# External_MIDI_Interface.net
KiCad netlist of a schematic drawn in EasyEDA
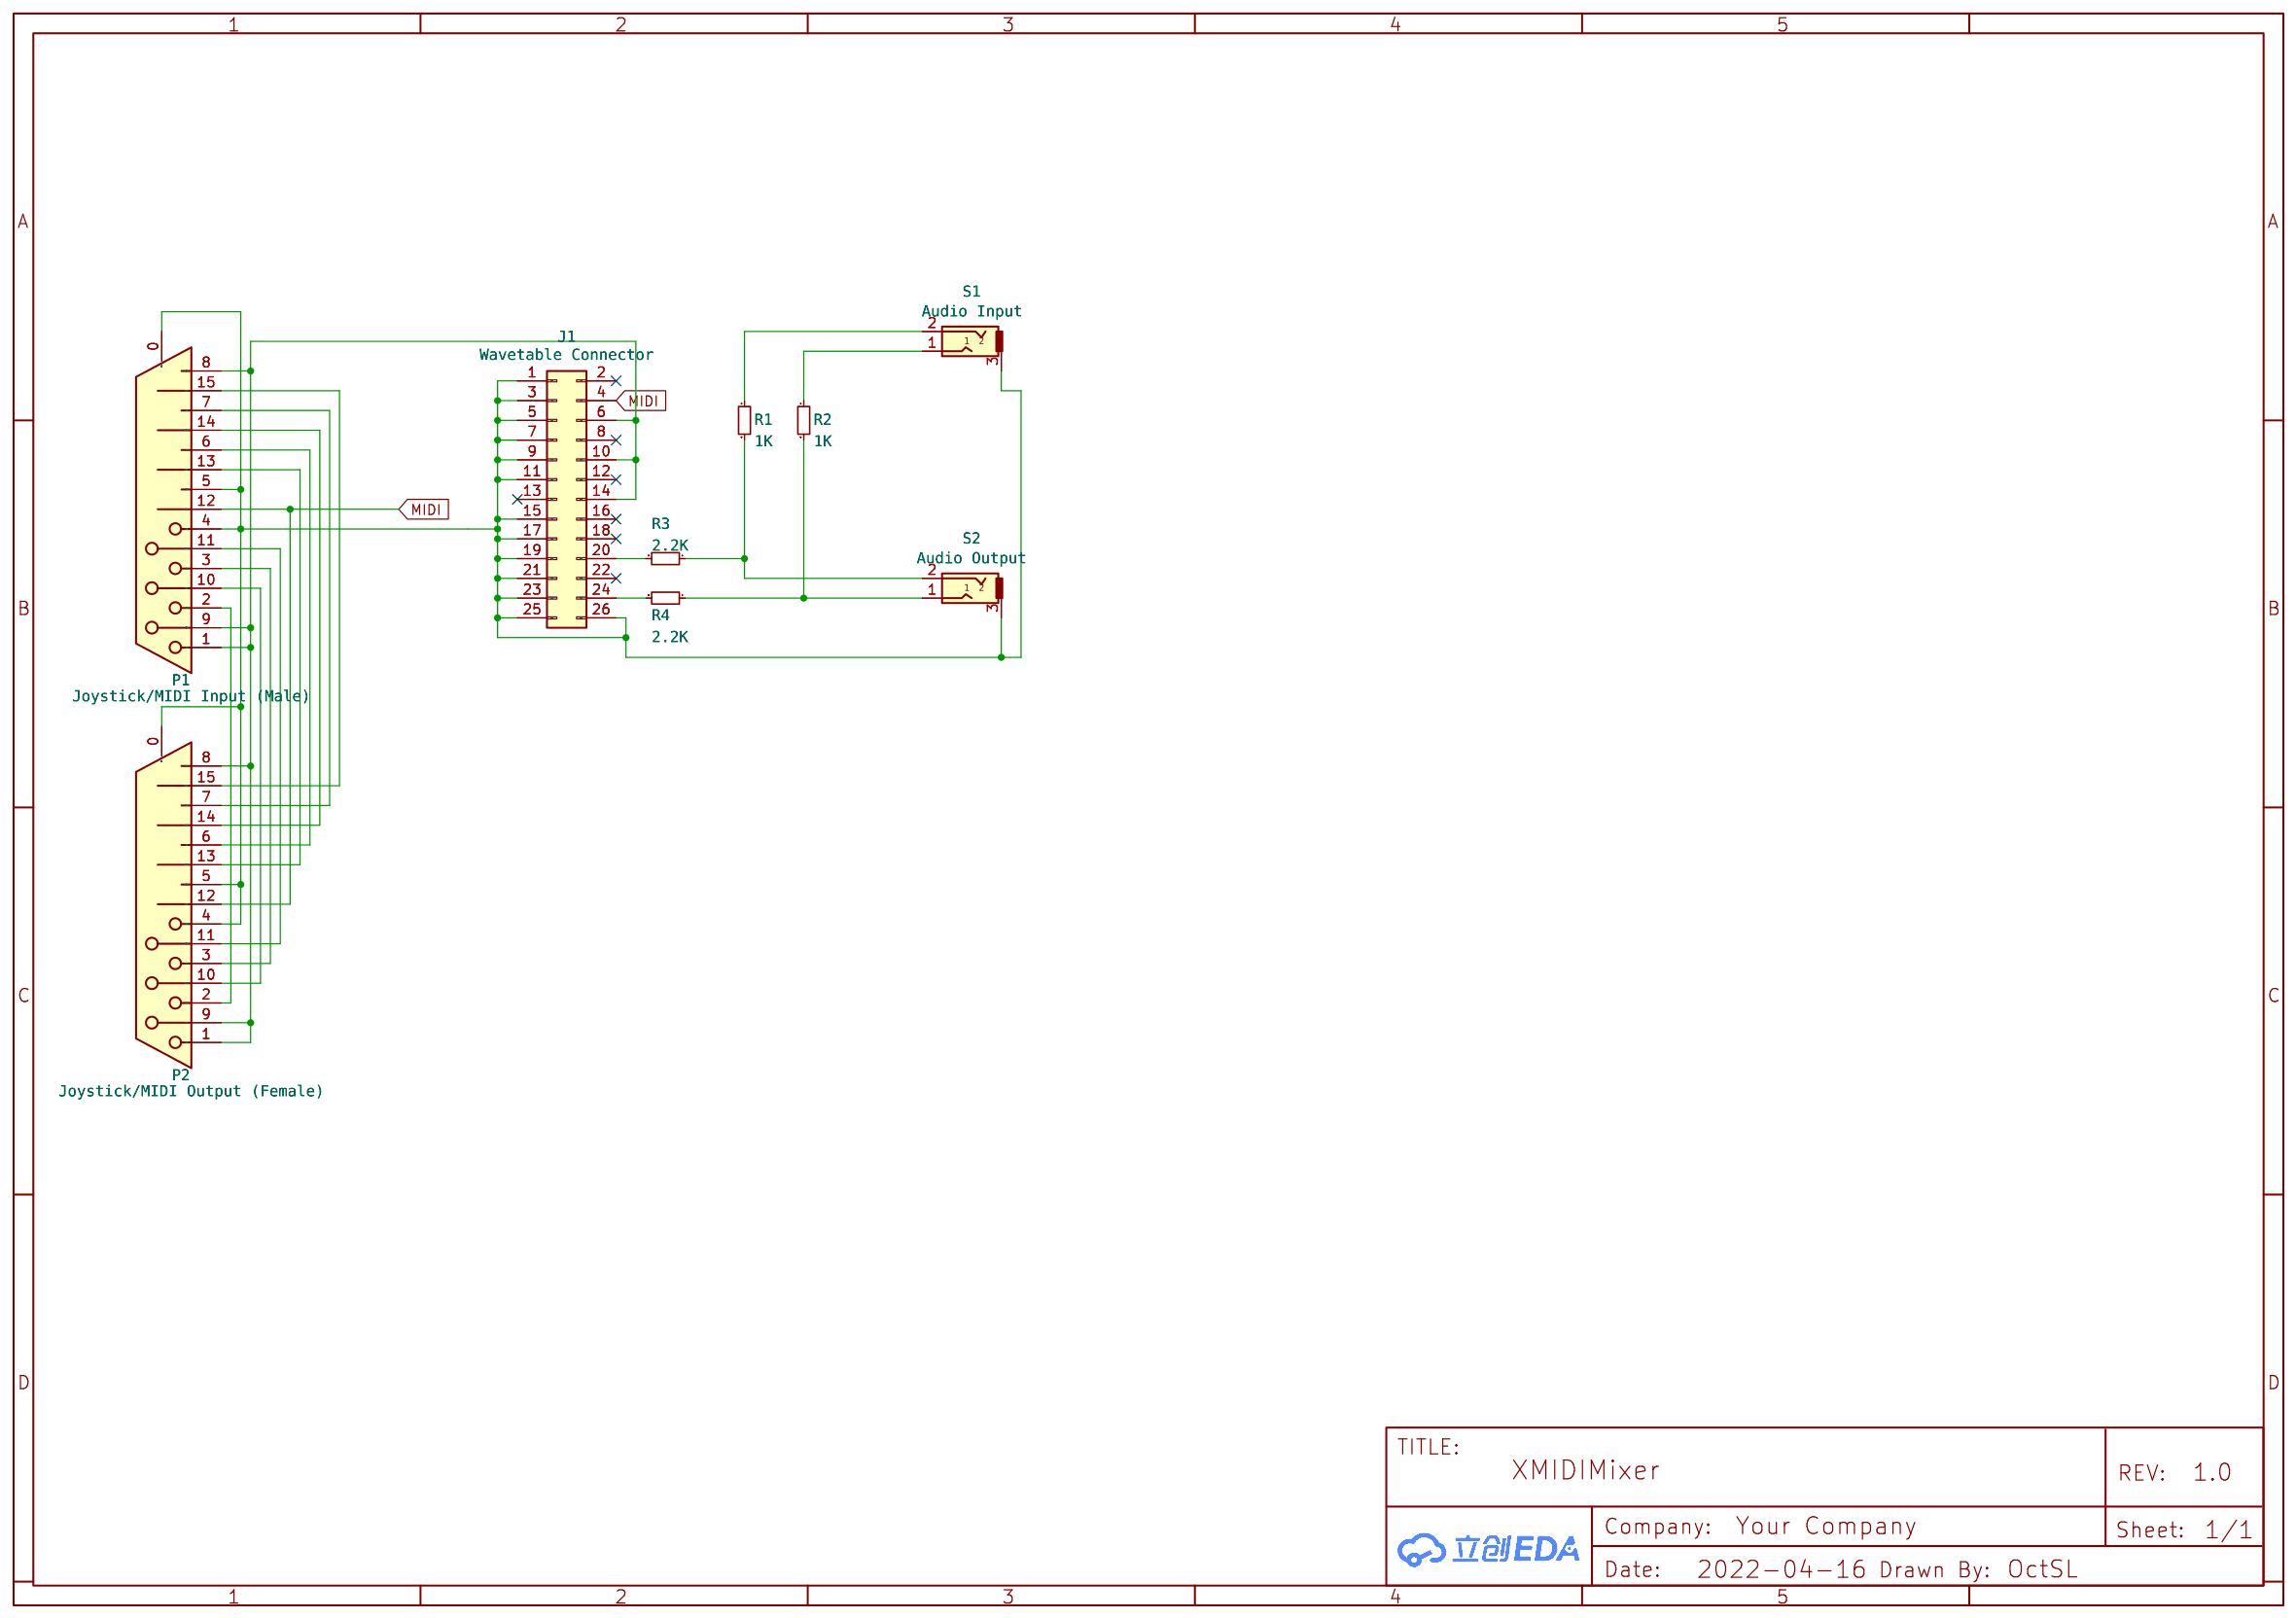
[diagram p0: schematic sheet]

(export (version "E")
  (design (tool "Eeschema 10.0.6"))
  (components
    (comp (ref "J1") (value "Wavetable Connector") (libsource (lib "") (part "Unknown_275_-560")))
    (comp (ref "P1") (value "Joystick/MIDI Input (Male)") (libsource (lib "") (part "Unknown_75_-555")))
    (comp (ref "P2") (value "Joystick/MIDI Output (Female)") (libsource (lib "") (part "Unknown_75_-355")))
    (comp (ref "R1") (value "1K") (libsource (lib "") (part "Unknown_370_-600")))
    (comp (ref "R2") (value "1K") (libsource (lib "") (part "Unknown_400_-600")))
    (comp (ref "R3") (value "2.2K") (libsource (lib "") (part "Unknown_330_-530")))
    (comp (ref "R4") (value "2.2K") (libsource (lib "") (part "Unknown_330_-510")))
    (comp (ref "S1") (value "Audio Input") (libsource (lib "") (part "Unknown_480_-635")))
    (comp (ref "S2") (value "Audio Output") (libsource (lib "") (part "Unknown_480_-510")))
  )
  (nets
    (net (code "1") (name "MIDI") (class "Default")
      (node (ref "J1") (pin "4") (pinfunction "Pin_4_4") (pintype "unspecified"))
      (node (ref "P1") (pin "12") (pinfunction "P12_12") (pintype "unspecified"))
      (node (ref "P2") (pin "12") (pinfunction "P12_12") (pintype "unspecified"))
    )
    (net (code "2") (name "Net-(J1-Pin_1)") (class "Default")
      (node (ref "J1") (pin "1") (pinfunction "Pin_1_1") (pintype "unspecified"))
      (node (ref "J1") (pin "11") (pinfunction "Pin_11_11") (pintype "unspecified"))
      (node (ref "J1") (pin "15") (pinfunction "Pin_15_15") (pintype "unspecified"))
      (node (ref "J1") (pin "17") (pinfunction "Pin_17_17") (pintype "unspecified"))
      (node (ref "J1") (pin "19") (pinfunction "Pin_19_19") (pintype "unspecified"))
      (node (ref "J1") (pin "21") (pinfunction "Pin_21_21") (pintype "unspecified"))
      (node (ref "J1") (pin "23") (pinfunction "Pin_23_23") (pintype "unspecified"))
      (node (ref "J1") (pin "25") (pinfunction "Pin_25_25") (pintype "unspecified"))
      (node (ref "J1") (pin "26") (pinfunction "Pin_26_26") (pintype "unspecified"))
      (node (ref "J1") (pin "3") (pinfunction "Pin_3_3") (pintype "unspecified"))
      (node (ref "J1") (pin "5") (pinfunction "Pin_5_5") (pintype "unspecified"))
      (node (ref "J1") (pin "7") (pinfunction "Pin_7_7") (pintype "unspecified"))
      (node (ref "J1") (pin "9") (pinfunction "Pin_9_9") (pintype "unspecified"))
      (node (ref "P1") (pin "0") (pinfunction "PAD_0") (pintype "unspecified"))
      (node (ref "P1") (pin "4") (pinfunction "4_4") (pintype "unspecified"))
      (node (ref "P1") (pin "5") (pinfunction "5_5") (pintype "unspecified"))
      (node (ref "P2") (pin "0") (pinfunction "PAD_0") (pintype "unspecified"))
      (node (ref "P2") (pin "4") (pinfunction "4_4") (pintype "unspecified"))
      (node (ref "P2") (pin "5") (pinfunction "5_5") (pintype "unspecified"))
      (node (ref "S1") (pin "3") (pintype "unspecified"))
      (node (ref "S2") (pin "3") (pintype "unspecified"))
    )
    (net (code "3") (name "Net-(J1-Pin_10)") (class "Default")
      (node (ref "J1") (pin "10") (pinfunction "Pin_10_10") (pintype "unspecified"))
      (node (ref "J1") (pin "14") (pinfunction "Pin_14_14") (pintype "unspecified"))
      (node (ref "J1") (pin "6") (pinfunction "Pin_6_6") (pintype "unspecified"))
      (node (ref "P1") (pin "1") (pinfunction "1_1") (pintype "unspecified"))
      (node (ref "P1") (pin "8") (pinfunction "8_8") (pintype "unspecified"))
      (node (ref "P1") (pin "9") (pinfunction "P9_9") (pintype "unspecified"))
      (node (ref "P2") (pin "1") (pinfunction "1_1") (pintype "unspecified"))
      (node (ref "P2") (pin "8") (pinfunction "8_8") (pintype "unspecified"))
      (node (ref "P2") (pin "9") (pinfunction "P9_9") (pintype "unspecified"))
    )
    (net (code "4") (name "Net-(J1-Pin_20)") (class "Default")
      (node (ref "J1") (pin "20") (pinfunction "Pin_20_20") (pintype "unspecified"))
      (node (ref "R3") (pin "2") (pintype "unspecified"))
    )
    (net (code "5") (name "Net-(J1-Pin_24)") (class "Default")
      (node (ref "J1") (pin "24") (pinfunction "Pin_24_24") (pintype "unspecified"))
      (node (ref "R4") (pin "2") (pintype "unspecified"))
    )
    (net (code "6") (name "Net-(P1-P10)") (class "Default")
      (node (ref "P1") (pin "10") (pinfunction "P10_10") (pintype "unspecified"))
      (node (ref "P2") (pin "10") (pinfunction "P10_10") (pintype "unspecified"))
    )
    (net (code "7") (name "Net-(P1-P13)") (class "Default")
      (node (ref "P1") (pin "13") (pinfunction "P13_13") (pintype "unspecified"))
      (node (ref "P2") (pin "13") (pinfunction "P13_13") (pintype "unspecified"))
    )
    (net (code "8") (name "Net-(P1-P14)") (class "Default")
      (node (ref "P1") (pin "14") (pinfunction "P14_14") (pintype "unspecified"))
      (node (ref "P2") (pin "14") (pinfunction "P14_14") (pintype "unspecified"))
    )
    (net (code "9") (name "Net-(P1-P15)") (class "Default")
      (node (ref "P1") (pin "15") (pinfunction "P15_15") (pintype "unspecified"))
      (node (ref "P2") (pin "15") (pinfunction "P15_15") (pintype "unspecified"))
    )
    (net (code "10") (name "Net-(P1-P111)") (class "Default")
      (node (ref "P1") (pin "11") (pinfunction "P111_11") (pintype "unspecified"))
      (node (ref "P2") (pin "11") (pinfunction "P111_11") (pintype "unspecified"))
    )
    (net (code "11") (name "Net-(P1-Pad2)") (class "Default")
      (node (ref "P1") (pin "2") (pinfunction "2_2") (pintype "unspecified"))
      (node (ref "P2") (pin "2") (pinfunction "2_2") (pintype "unspecified"))
    )
    (net (code "12") (name "Net-(P1-Pad3)") (class "Default")
      (node (ref "P1") (pin "3") (pinfunction "3_3") (pintype "unspecified"))
      (node (ref "P2") (pin "3") (pinfunction "3_3") (pintype "unspecified"))
    )
    (net (code "13") (name "Net-(P1-Pad6)") (class "Default")
      (node (ref "P1") (pin "6") (pinfunction "6_6") (pintype "unspecified"))
      (node (ref "P2") (pin "6") (pinfunction "6_6") (pintype "unspecified"))
    )
    (net (code "14") (name "Net-(P1-Pad7)") (class "Default")
      (node (ref "P1") (pin "7") (pinfunction "7_7") (pintype "unspecified"))
      (node (ref "P2") (pin "7") (pinfunction "7_7") (pintype "unspecified"))
    )
    (net (code "15") (name "Net-(R1-Pad1)") (class "Default")
      (node (ref "R1") (pin "1") (pintype "unspecified"))
      (node (ref "S1") (pin "2") (pintype "unspecified"))
    )
    (net (code "16") (name "Net-(R1-Pad2)") (class "Default")
      (node (ref "R1") (pin "2") (pintype "unspecified"))
      (node (ref "R3") (pin "1") (pintype "unspecified"))
      (node (ref "S2") (pin "2") (pintype "unspecified"))
    )
    (net (code "17") (name "Net-(R2-Pad1)") (class "Default")
      (node (ref "R2") (pin "1") (pintype "unspecified"))
      (node (ref "S1") (pin "1") (pintype "unspecified"))
    )
    (net (code "18") (name "Net-(R2-Pad2)") (class "Default")
      (node (ref "R2") (pin "2") (pintype "unspecified"))
      (node (ref "R4") (pin "1") (pintype "unspecified"))
      (node (ref "S2") (pin "1") (pintype "unspecified"))
    )
    (net (code "19") (name "unconnected-(J1-Pin_2-Pad2)") (class "Default")
      (node (ref "J1") (pin "2") (pinfunction "Pin_2_2") (pintype "unspecified+no_connect"))
    )
    (net (code "20") (name "unconnected-(J1-Pin_8-Pad8)") (class "Default")
      (node (ref "J1") (pin "8") (pinfunction "Pin_8_8") (pintype "unspecified+no_connect"))
    )
    (net (code "21") (name "unconnected-(J1-Pin_12-Pad12)") (class "Default")
      (node (ref "J1") (pin "12") (pinfunction "Pin_12_12") (pintype "unspecified+no_connect"))
    )
    (net (code "22") (name "unconnected-(J1-Pin_13-Pad13)") (class "Default")
      (node (ref "J1") (pin "13") (pinfunction "Pin_13_13") (pintype "unspecified+no_connect"))
    )
    (net (code "23") (name "unconnected-(J1-Pin_16-Pad16)") (class "Default")
      (node (ref "J1") (pin "16") (pinfunction "Pin_16_16") (pintype "unspecified+no_connect"))
    )
    (net (code "24") (name "unconnected-(J1-Pin_18-Pad18)") (class "Default")
      (node (ref "J1") (pin "18") (pinfunction "Pin_18_18") (pintype "unspecified+no_connect"))
    )
    (net (code "25") (name "unconnected-(J1-Pin_22-Pad22)") (class "Default")
      (node (ref "J1") (pin "22") (pinfunction "Pin_22_22") (pintype "unspecified+no_connect"))
    )
  )
)
